# PWR.net
KiCad netlist of a schematic drawn in Altium Designer
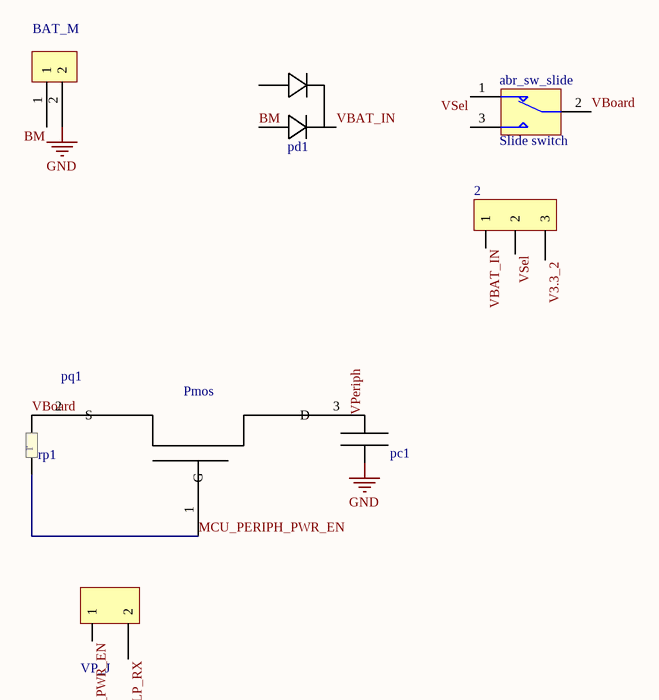
[diagram p0: PWR.SchDoc]

(export (version "E")
  (design (tool "Eeschema 10.0.6"))
  (components
    (comp (ref "2")
      (value "pin header 2mm")
      (footprint "abr_ph_3x1_2mm_2d_male")
      (libsource (lib "abr_ph_2mm_96_02") (part "abr_ph_3x1_2mm"))
    )
    (comp (ref "abr_sw_slide")
      (value "Slide switch")
      (footprint "abr_sw_slide__r_3d")
      (libsource (lib "lpwireless") (part "Slide switch"))
    )
    (comp (ref "BAT_M")
      (value "YB2 SMD")
      (footprint "abr_sw_yb_2p_3d")
      (libsource (lib "lpwireless") (part "YB2 SMD"))
    )
    (comp (ref "pc1")
      (value "100nf")
      (footprint "abr_cap_0805_3d")
      (libsource (lib "abr_smd_0805_all") (part "abr_cap_0805"))
    )
    (comp (ref "pd1")
      (value "abr_diode_shotkey")
      (footprint "abr_diode_bat54c_3d")
      (libsource (lib "abr_diode_smd") (part "abr_diode_shatkey_bat54c"))
    )
    (comp (ref "pq1")
      (value "irlm6402")
      (footprint "irlm6402")
      (libsource (lib "abr_transistor_smd") (part "irlm6402"))
    )
    (comp (ref "rp1")
      (value "100k")
      (footprint "abr_res_0805_3d")
      (libsource (lib "abr_smd_0805_all") (part "abr_res_0805"))
    )
    (comp (ref "VP_J")
      (value "pin header 2mm")
      (footprint "abr_ph_2x1_2mm_3d_male")
      (libsource (lib "abr_ph_2mm_96_02") (part "abr_2x1_2mm"))
    )
  )
  (nets
    (net (code "1") (name "/BM") (class "Default")
      (node (ref "BAT_M") (pin "1") (pinfunction "1_1") (pintype "passive"))
      (node (ref "pd1") (pin "2") (pinfunction "2_2") (pintype "passive"))
    )
    (net (code "2") (name "/MCULP_RX") (class "Default")
      (node (ref "VP_J") (pin "2") (pinfunction "2_2") (pintype "passive"))
    )
    (net (code "3") (name "/MCU_PERIPH_PWR_EN") (class "Default")
      (node (ref "VP_J") (pin "1") (pinfunction "1_1") (pintype "passive"))
      (node (ref "pq1") (pin "1") (pinfunction "G_1") (pintype "passive"))
      (node (ref "rp1") (pin "0") (pinfunction "0_0") (pintype "passive"))
    )
    (net (code "4") (name "/V3.3_2") (class "Default")
      (node (ref "2") (pin "3") (pinfunction "3_3") (pintype "passive"))
    )
    (net (code "5") (name "/VBAT_IN") (class "Default")
      (node (ref "2") (pin "1") (pinfunction "1_1") (pintype "passive"))
      (node (ref "pd1") (pin "3") (pinfunction "5_3") (pintype "passive"))
    )
    (net (code "6") (name "/VBoard") (class "Default")
      (node (ref "abr_sw_slide") (pin "2") (pinfunction "2_2") (pintype "passive"))
      (node (ref "pq1") (pin "2") (pinfunction "S_2") (pintype "passive"))
      (node (ref "rp1") (pin "1") (pinfunction "0_1") (pintype "passive"))
    )
    (net (code "7") (name "/VPeriph") (class "Default")
      (node (ref "pc1") (pin "0") (pinfunction "2_0") (pintype "passive"))
      (node (ref "pq1") (pin "3") (pinfunction "D_3") (pintype "passive"))
    )
    (net (code "8") (name "/VSel") (class "Default")
      (node (ref "2") (pin "2") (pinfunction "2_2") (pintype "passive"))
      (node (ref "abr_sw_slide") (pin "1") (pinfunction "1_1") (pintype "passive"))
    )
    (net (code "9") (name "GND") (class "Default")
      (node (ref "BAT_M") (pin "2") (pinfunction "2_2") (pintype "passive"))
      (node (ref "pc1") (pin "1") (pinfunction "10_1") (pintype "passive"))
    )
    (net (code "10") (name "unconnected-(abr_sw_slide-Pad3)") (class "Default")
      (node (ref "abr_sw_slide") (pin "3") (pinfunction "3_3") (pintype "passive"))
    )
    (net (code "11") (name "unconnected-(pd1-4-Pad1)") (class "Default")
      (node (ref "pd1") (pin "1") (pinfunction "4_1") (pintype "passive"))
    )
  )
)
